# SCH_GSME_voltmeter_Arduino_ESP8266_TP405.net
KiCad netlist of a schematic drawn in EasyEDA
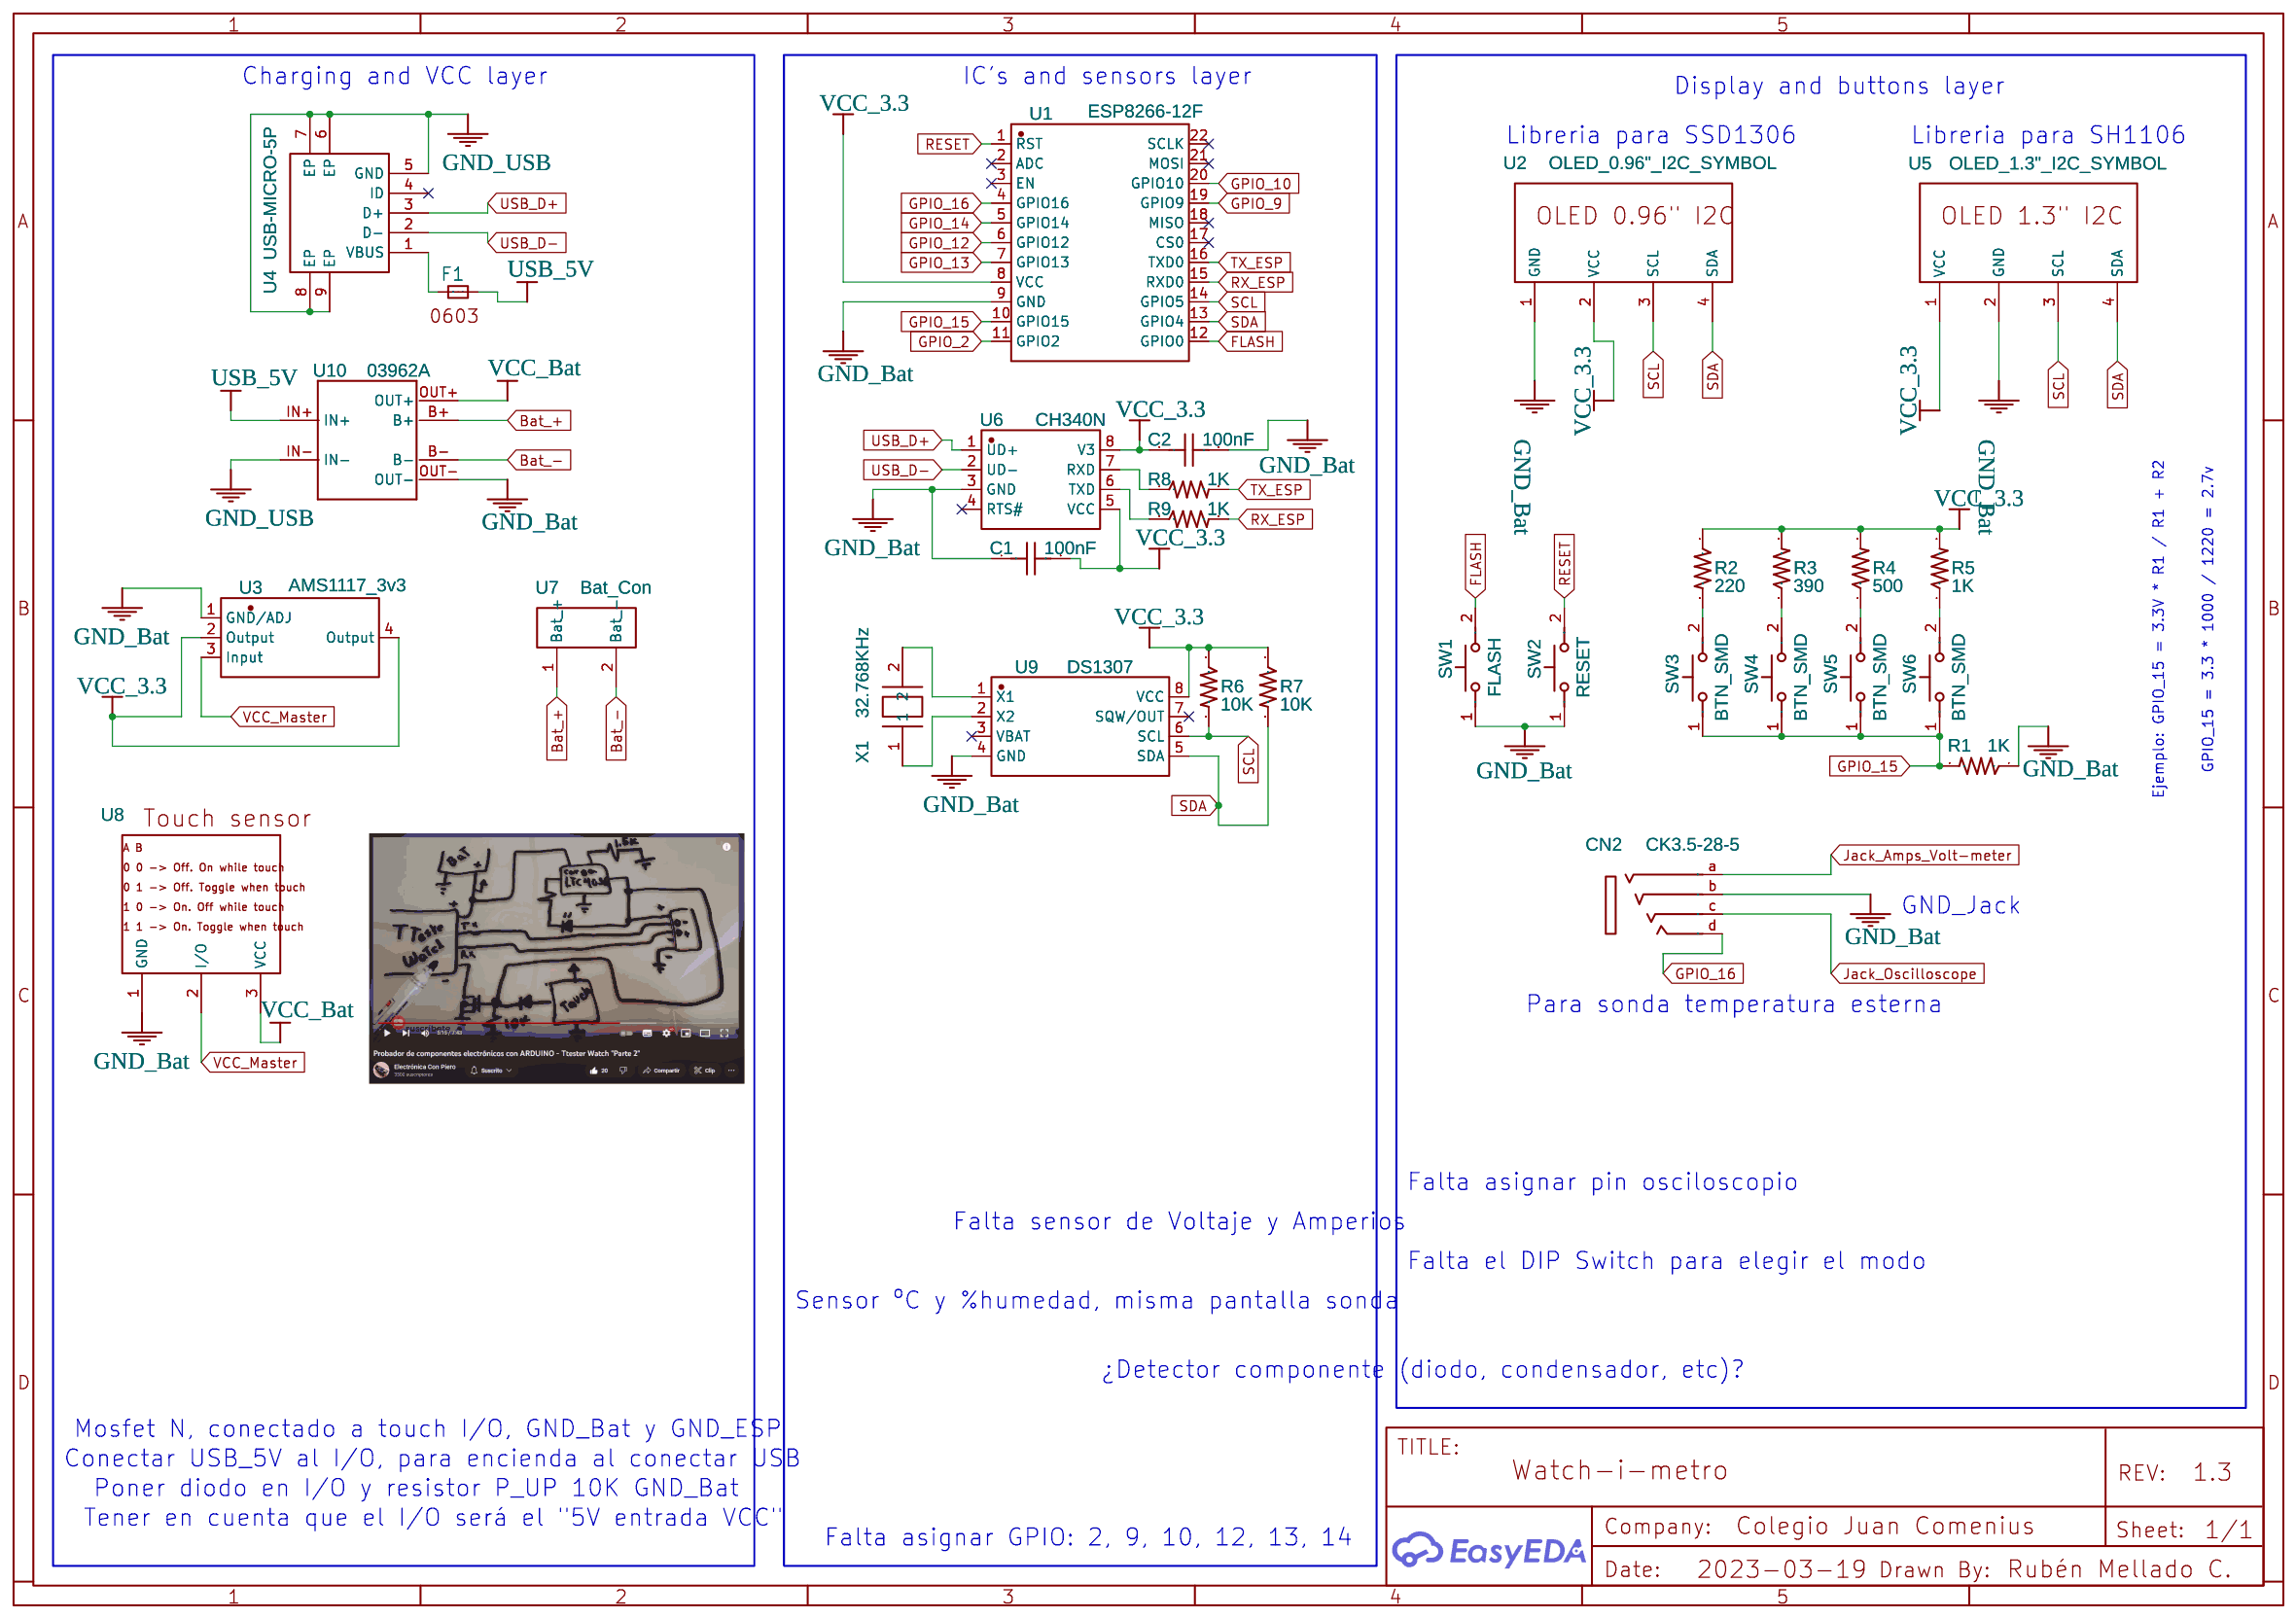
[diagram p0: schematic sheet]

(export (version "E")
  (design (tool "Eeschema 10.0.6"))
  (components
    (comp (ref "C1") (value "100nF") (libsource (lib "") (part "C_0603_US")))
    (comp (ref "C2") (value "100nF") (libsource (lib "") (part "C_0603_US")))
    (comp (ref "CN2")
      (value "CK3.5-28-5")
      (fields (field (name "BOM_Supplier Part") "C718048"))
      (libsource (lib "") (part "CK3.5-28-5"))
    )
    (comp (ref "F1")
      (value "Fuse")
      (fields (field (name "BOM_Manufacturer Part") "0603") (field (name "BOM_Supplier Part") "C9900014602"))
      (libsource (lib "") (part "0603_FUSE_SYMBOL"))
    )
    (comp (ref "R1") (value "1K") (libsource (lib "") (part "RESISTOR0603")))
    (comp (ref "R2") (value "220") (libsource (lib "") (part "RESISTOR0603_1")))
    (comp (ref "R3") (value "390") (libsource (lib "") (part "RESISTOR0603_3")))
    (comp (ref "R4") (value "500") (libsource (lib "") (part "RESISTOR0603_3")))
    (comp (ref "R5") (value "1K") (libsource (lib "") (part "RESISTOR0603_3")))
    (comp (ref "R6") (value "10K") (libsource (lib "") (part "RESISTOR0603_1")))
    (comp (ref "R7") (value "10K") (libsource (lib "") (part "RESISTOR0603_1")))
    (comp (ref "R8") (value "1K") (libsource (lib "") (part "RESISTOR0603_2")))
    (comp (ref "R9") (value "1K") (libsource (lib "") (part "RESISTOR0603_2")))
    (comp (ref "SW1")
      (value "FLASH")
      (fields
        (field (name "BOM_Manufacturer Part") "BUTTON2")
        (field (name "BOM_Supplier Part") "C9900005988")
      )
      (libsource (lib "") (part "BUTTON2"))
    )
    (comp (ref "SW2")
      (value "RESET")
      (fields
        (field (name "BOM_Manufacturer Part") "BUTTON2")
        (field (name "BOM_Supplier Part") "C9900005988")
      )
      (libsource (lib "") (part "BUTTON2"))
    )
    (comp (ref "SW3")
      (value "BTN_SMD")
      (fields
        (field (name "BOM_Manufacturer Part") "BUTTON2")
        (field (name "BOM_Supplier Part") "C9900005988")
      )
      (libsource (lib "") (part "BUTTON2"))
    )
    (comp (ref "SW4")
      (value "BTN_SMD")
      (fields
        (field (name "BOM_Manufacturer Part") "BUTTON2")
        (field (name "BOM_Supplier Part") "C9900005988")
      )
      (libsource (lib "") (part "BUTTON2"))
    )
    (comp (ref "SW5")
      (value "BTN_SMD")
      (fields
        (field (name "BOM_Manufacturer Part") "BUTTON2")
        (field (name "BOM_Supplier Part") "C9900005988")
      )
      (libsource (lib "") (part "BUTTON2"))
    )
    (comp (ref "SW6")
      (value "BTN_SMD")
      (fields
        (field (name "BOM_Manufacturer Part") "BUTTON2")
        (field (name "BOM_Supplier Part") "C9900005988")
      )
      (libsource (lib "") (part "BUTTON2"))
    )
    (comp (ref "U1")
      (value "ESP8266-12F")
      (fields
        (field (name "BOM_Manufacturer Part") "ESP-12F(ESP8266MOD)")
        (field (name "BOM_Supplier Part") "C82891")
      )
      (libsource (lib "") (part "ESP-12F(ESP8266MOD)"))
    )
    (comp (ref "U2")
      (value "OLED_0.96\"_I2C_SYMBOL")
      (libsource (lib "") (part "OLED_0.96{dblquote}_I2C_SYMBOL"))
    )
    (comp (ref "U3")
      (value "AMS1117_3v3")
      (fields
        (field (name "BOM_Manufacturer Part") "AMS1117-3.3S")
        (field (name "BOM_Supplier Part") "C2842296")
      )
      (libsource (lib "") (part "AMS1117-3.3S"))
    )
    (comp (ref "U4")
      (value "USB-MICRO-5P")
      (fields
        (field (name "BOM_Manufacturer Part") "USB-Micro-5P")
        (field (name "BOM_Supplier Part") "C9900014288")
      )
      (libsource (lib "") (part "USB-MICRO-5P"))
    )
    (comp (ref "U5")
      (value "OLED_1.3\"_I2C_SYMBOL")
      (libsource (lib "") (part "OLED_1.3{dblquote}_I2C_SYMBOL"))
    )
    (comp (ref "U6")
      (value "CH340N")
      (fields (field (name "BOM_Supplier Part") "C506813"))
      (libsource (lib "") (part "CH340N"))
    )
    (comp (ref "U7") (value "Bat_Con") (libsource (lib "") (part "Connector_Battery_2_Wires_2p")))
    (comp (ref "U8") (value "Touch_Sensor") (libsource (lib "") (part "Touch_Sensor_3p_A_B_SYMBOL")))
    (comp (ref "U9")
      (value "DS1307")
      (fields
        (field (name "BOM_Manufacturer Part") "DS1307M/TR")
        (field (name "BOM_Supplier Part") "C356706")
      )
      (libsource (lib "") (part "DS1307M/TR"))
    )
    (comp (ref "U10") (value "03962A") (libsource (lib "") (part "03962A")))
    (comp (ref "X1") (value "32.768KHz") (libsource (lib "") (part "Quartz_X_2p_Symbol")))
  )
  (nets
    (net (code "1") (name "Bat_+") (class "Default")
      (node (ref "U10") (pin "B+") (pinfunction "B+_B+") (pintype "bidirectional"))
      (node (ref "U7") (pin "1") (pinfunction "Bat_+_1") (pintype "unspecified"))
    )
    (net (code "2") (name "Bat_-") (class "Default")
      (node (ref "U10") (pin "B-") (pinfunction "B-_B-") (pintype "bidirectional"))
      (node (ref "U7") (pin "2") (pinfunction "Bat_-_2") (pintype "unspecified"))
    )
    (net (code "3") (name "FLASH") (class "Default")
      (node (ref "SW1") (pin "2") (pinfunction "2_2") (pintype "unspecified"))
      (node (ref "U1") (pin "12") (pinfunction "GPIO0_12") (pintype "unspecified"))
    )
    (net (code "4") (name "GND_Bat") (class "Default")
      (node (ref "C1") (pin "1") (pinfunction "1_1") (pintype "unspecified"))
      (node (ref "C2") (pin "2") (pinfunction "2_2") (pintype "unspecified"))
      (node (ref "CN2") (pin "b") (pinfunction "b_b") (pintype "unspecified"))
      (node (ref "R1") (pin "1") (pinfunction "1_1") (pintype "unspecified"))
      (node (ref "SW1") (pin "1") (pinfunction "1_1") (pintype "unspecified"))
      (node (ref "SW2") (pin "1") (pinfunction "1_1") (pintype "unspecified"))
      (node (ref "U1") (pin "9") (pinfunction "GND_9") (pintype "unspecified"))
      (node (ref "U10") (pin "OUT-") (pinfunction "OUT-_OUT-") (pintype "bidirectional"))
      (node (ref "U2") (pin "1") (pinfunction "GND_1") (pintype "unspecified"))
      (node (ref "U3") (pin "1") (pinfunction "GND/ADJ_1") (pintype "unspecified"))
      (node (ref "U5") (pin "2") (pinfunction "GND_2") (pintype "unspecified"))
      (node (ref "U6") (pin "3") (pinfunction "GND_3") (pintype "unspecified"))
      (node (ref "U8") (pin "1") (pinfunction "GND_1") (pintype "unspecified"))
      (node (ref "U9") (pin "4") (pinfunction "GND_4") (pintype "unspecified"))
    )
    (net (code "5") (name "GND_USB") (class "Default")
      (node (ref "U10") (pin "IN-") (pinfunction "IN-_IN-") (pintype "bidirectional"))
      (node (ref "U4") (pin "5") (pinfunction "GND_5") (pintype "unspecified"))
      (node (ref "U4") (pin "6") (pinfunction "EP_6") (pintype "unspecified"))
      (node (ref "U4") (pin "7") (pinfunction "EP_7") (pintype "unspecified"))
      (node (ref "U4") (pin "8") (pinfunction "EP_8") (pintype "unspecified"))
      (node (ref "U4") (pin "9") (pinfunction "EP_9") (pintype "unspecified"))
    )
    (net (code "6") (name "GPIO_2") (class "Default")
      (node (ref "U1") (pin "11") (pinfunction "GPIO2_11") (pintype "unspecified"))
    )
    (net (code "7") (name "GPIO_9") (class "Default")
      (node (ref "U1") (pin "19") (pinfunction "GPIO9_19") (pintype "unspecified"))
    )
    (net (code "8") (name "GPIO_10") (class "Default")
      (node (ref "U1") (pin "20") (pinfunction "GPIO10_20") (pintype "unspecified"))
    )
    (net (code "9") (name "GPIO_12") (class "Default")
      (node (ref "U1") (pin "6") (pinfunction "GPIO12_6") (pintype "unspecified"))
    )
    (net (code "10") (name "GPIO_13") (class "Default")
      (node (ref "U1") (pin "7") (pinfunction "GPIO13_7") (pintype "unspecified"))
    )
    (net (code "11") (name "GPIO_14") (class "Default")
      (node (ref "U1") (pin "5") (pinfunction "GPIO14_5") (pintype "unspecified"))
    )
    (net (code "12") (name "GPIO_15") (class "Default")
      (node (ref "R1") (pin "2") (pinfunction "2_2") (pintype "unspecified"))
      (node (ref "SW3") (pin "1") (pinfunction "1_1") (pintype "unspecified"))
      (node (ref "SW4") (pin "1") (pinfunction "1_1") (pintype "unspecified"))
      (node (ref "SW5") (pin "1") (pinfunction "1_1") (pintype "unspecified"))
      (node (ref "SW6") (pin "1") (pinfunction "1_1") (pintype "unspecified"))
      (node (ref "U1") (pin "10") (pinfunction "GPIO15_10") (pintype "unspecified"))
    )
    (net (code "13") (name "GPIO_16") (class "Default")
      (node (ref "CN2") (pin "d") (pinfunction "d_d") (pintype "unspecified"))
      (node (ref "U1") (pin "4") (pinfunction "GPIO16_4") (pintype "unspecified"))
    )
    (net (code "14") (name "Jack_Amps_Volt-meter") (class "Default")
      (node (ref "CN2") (pin "a") (pinfunction "a_a") (pintype "unspecified"))
    )
    (net (code "15") (name "Jack_Oscilloscope") (class "Default")
      (node (ref "CN2") (pin "c") (pinfunction "c_c") (pintype "unspecified"))
    )
    (net (code "16") (name "Net-(F1-K)") (class "Default")
      (node (ref "F1") (pin "1") (pinfunction "K_1") (pintype "unspecified"))
      (node (ref "U4") (pin "1") (pinfunction "VBUS_1") (pintype "unspecified"))
    )
    (net (code "17") (name "Net-(R2-Pad2)") (class "Default")
      (node (ref "R2") (pin "2") (pinfunction "2_2") (pintype "unspecified"))
      (node (ref "SW3") (pin "2") (pinfunction "2_2") (pintype "unspecified"))
    )
    (net (code "18") (name "Net-(R3-Pad1)") (class "Default")
      (node (ref "R3") (pin "1") (pinfunction "1_1") (pintype "unspecified"))
      (node (ref "SW4") (pin "2") (pinfunction "2_2") (pintype "unspecified"))
    )
    (net (code "19") (name "Net-(R4-Pad1)") (class "Default")
      (node (ref "R4") (pin "1") (pinfunction "1_1") (pintype "unspecified"))
      (node (ref "SW5") (pin "2") (pinfunction "2_2") (pintype "unspecified"))
    )
    (net (code "20") (name "Net-(R5-Pad1)") (class "Default")
      (node (ref "R5") (pin "1") (pinfunction "1_1") (pintype "unspecified"))
      (node (ref "SW6") (pin "2") (pinfunction "2_2") (pintype "unspecified"))
    )
    (net (code "21") (name "Net-(U6-RXD)") (class "Default")
      (node (ref "R8") (pin "1") (pinfunction "1_1") (pintype "unspecified"))
      (node (ref "U6") (pin "7") (pinfunction "RXD_7") (pintype "unspecified"))
    )
    (net (code "22") (name "Net-(U6-TXD)") (class "Default")
      (node (ref "R9") (pin "1") (pinfunction "1_1") (pintype "unspecified"))
      (node (ref "U6") (pin "6") (pinfunction "TXD_6") (pintype "unspecified"))
    )
    (net (code "23") (name "Net-(U9-X1)") (class "Default")
      (node (ref "U9") (pin "1") (pinfunction "X1_1") (pintype "unspecified"))
      (node (ref "X1") (pin "2") (pinfunction "2_2") (pintype "unspecified"))
    )
    (net (code "24") (name "Net-(U9-X2)") (class "Default")
      (node (ref "U9") (pin "2") (pinfunction "X2_2") (pintype "unspecified"))
      (node (ref "X1") (pin "1") (pinfunction "1_1") (pintype "unspecified"))
    )
    (net (code "25") (name "RESET") (class "Default")
      (node (ref "SW2") (pin "2") (pinfunction "2_2") (pintype "unspecified"))
      (node (ref "U1") (pin "1") (pinfunction "RST_1") (pintype "unspecified"))
    )
    (net (code "26") (name "RX_ESP") (class "Default")
      (node (ref "R9") (pin "2") (pinfunction "2_2") (pintype "unspecified"))
      (node (ref "U1") (pin "15") (pinfunction "RXD0_15") (pintype "unspecified"))
    )
    (net (code "27") (name "SCL") (class "Default")
      (node (ref "R6") (pin "2") (pinfunction "2_2") (pintype "unspecified"))
      (node (ref "U1") (pin "14") (pinfunction "GPIO5_14") (pintype "unspecified"))
      (node (ref "U2") (pin "3") (pinfunction "SCL_3") (pintype "unspecified"))
      (node (ref "U5") (pin "3") (pinfunction "SCL_3") (pintype "unspecified"))
      (node (ref "U9") (pin "6") (pinfunction "SCL_6") (pintype "unspecified"))
    )
    (net (code "28") (name "SDA") (class "Default")
      (node (ref "R7") (pin "2") (pinfunction "2_2") (pintype "unspecified"))
      (node (ref "U1") (pin "13") (pinfunction "GPIO4_13") (pintype "unspecified"))
      (node (ref "U2") (pin "4") (pinfunction "SDA_4") (pintype "unspecified"))
      (node (ref "U5") (pin "4") (pinfunction "SDA_4") (pintype "unspecified"))
      (node (ref "U9") (pin "5") (pinfunction "SDA_5") (pintype "unspecified"))
    )
    (net (code "29") (name "TX_ESP") (class "Default")
      (node (ref "R8") (pin "2") (pinfunction "2_2") (pintype "unspecified"))
      (node (ref "U1") (pin "16") (pinfunction "TXD0_16") (pintype "unspecified"))
    )
    (net (code "30") (name "USB_5V") (class "Default")
      (node (ref "F1") (pin "2") (pinfunction "A_2") (pintype "unspecified"))
      (node (ref "U10") (pin "IN+") (pinfunction "IN+_IN+") (pintype "bidirectional"))
    )
    (net (code "31") (name "USB_D+") (class "Default")
      (node (ref "U4") (pin "3") (pinfunction "D+_3") (pintype "unspecified"))
      (node (ref "U6") (pin "1") (pinfunction "UD+_1") (pintype "unspecified"))
    )
    (net (code "32") (name "USB_D-") (class "Default")
      (node (ref "U4") (pin "2") (pinfunction "D-_2") (pintype "unspecified"))
      (node (ref "U6") (pin "2") (pinfunction "UD-_2") (pintype "unspecified"))
    )
    (net (code "33") (name "VCC_3.3") (class "Default")
      (node (ref "C1") (pin "2") (pinfunction "2_2") (pintype "unspecified"))
      (node (ref "C2") (pin "1") (pinfunction "1_1") (pintype "unspecified"))
      (node (ref "R2") (pin "1") (pinfunction "1_1") (pintype "unspecified"))
      (node (ref "R3") (pin "2") (pinfunction "2_2") (pintype "unspecified"))
      (node (ref "R4") (pin "2") (pinfunction "2_2") (pintype "unspecified"))
      (node (ref "R5") (pin "2") (pinfunction "2_2") (pintype "unspecified"))
      (node (ref "R6") (pin "1") (pinfunction "1_1") (pintype "unspecified"))
      (node (ref "R7") (pin "1") (pinfunction "1_1") (pintype "unspecified"))
      (node (ref "U1") (pin "8") (pinfunction "VCC_8") (pintype "unspecified"))
      (node (ref "U2") (pin "2") (pinfunction "VCC_2") (pintype "unspecified"))
      (node (ref "U3") (pin "2") (pinfunction "Output_2") (pintype "unspecified"))
      (node (ref "U3") (pin "4") (pinfunction "Output_4") (pintype "unspecified"))
      (node (ref "U5") (pin "1") (pinfunction "VCC_1") (pintype "unspecified"))
      (node (ref "U6") (pin "5") (pinfunction "VCC_5") (pintype "unspecified"))
      (node (ref "U6") (pin "8") (pinfunction "V3_8") (pintype "unspecified"))
      (node (ref "U9") (pin "8") (pinfunction "VCC_8") (pintype "unspecified"))
    )
    (net (code "34") (name "VCC_Bat") (class "Default")
      (node (ref "U10") (pin "OUT+") (pinfunction "OUT+_OUT+") (pintype "bidirectional"))
      (node (ref "U8") (pin "3") (pinfunction "VCC_3") (pintype "unspecified"))
    )
    (net (code "35") (name "VCC_Master") (class "Default")
      (node (ref "U3") (pin "3") (pinfunction "Input_3") (pintype "unspecified"))
      (node (ref "U8") (pin "2") (pinfunction "I/O_2") (pintype "unspecified"))
    )
    (net (code "36") (name "unconnected-(U1-ADC-Pad2)") (class "Default")
      (node (ref "U1") (pin "2") (pinfunction "ADC_2") (pintype "unspecified+no_connect"))
    )
    (net (code "37") (name "unconnected-(U1-CS0-Pad17)") (class "Default")
      (node (ref "U1") (pin "17") (pinfunction "CS0_17") (pintype "unspecified+no_connect"))
    )
    (net (code "38") (name "unconnected-(U1-EN-Pad3)") (class "Default")
      (node (ref "U1") (pin "3") (pinfunction "EN_3") (pintype "unspecified+no_connect"))
    )
    (net (code "39") (name "unconnected-(U1-MISO-Pad18)") (class "Default")
      (node (ref "U1") (pin "18") (pinfunction "MISO_18") (pintype "unspecified+no_connect"))
    )
    (net (code "40") (name "unconnected-(U1-MOSI-Pad21)") (class "Default")
      (node (ref "U1") (pin "21") (pinfunction "MOSI_21") (pintype "unspecified+no_connect"))
    )
    (net (code "41") (name "unconnected-(U1-SCLK-Pad22)") (class "Default")
      (node (ref "U1") (pin "22") (pinfunction "SCLK_22") (pintype "unspecified+no_connect"))
    )
    (net (code "42") (name "unconnected-(U4-ID-Pad4)") (class "Default")
      (node (ref "U4") (pin "4") (pinfunction "ID_4") (pintype "unspecified+no_connect"))
    )
    (net (code "43") (name "unconnected-(U6-RTS#-Pad4)") (class "Default")
      (node (ref "U6") (pin "4") (pinfunction "RTS#_4") (pintype "unspecified+no_connect"))
    )
    (net (code "44") (name "unconnected-(U9-SQW{slash}OUT-Pad7)") (class "Default")
      (node (ref "U9") (pin "7") (pinfunction "SQW/OUT_7") (pintype "unspecified+no_connect"))
    )
    (net (code "45") (name "unconnected-(U9-VBAT-Pad3)") (class "Default")
      (node (ref "U9") (pin "3") (pinfunction "VBAT_3") (pintype "unspecified+no_connect"))
    )
  )
)
